# vilnius_rev_B.net
KiCad netlist of a schematic drawn in EAGLE
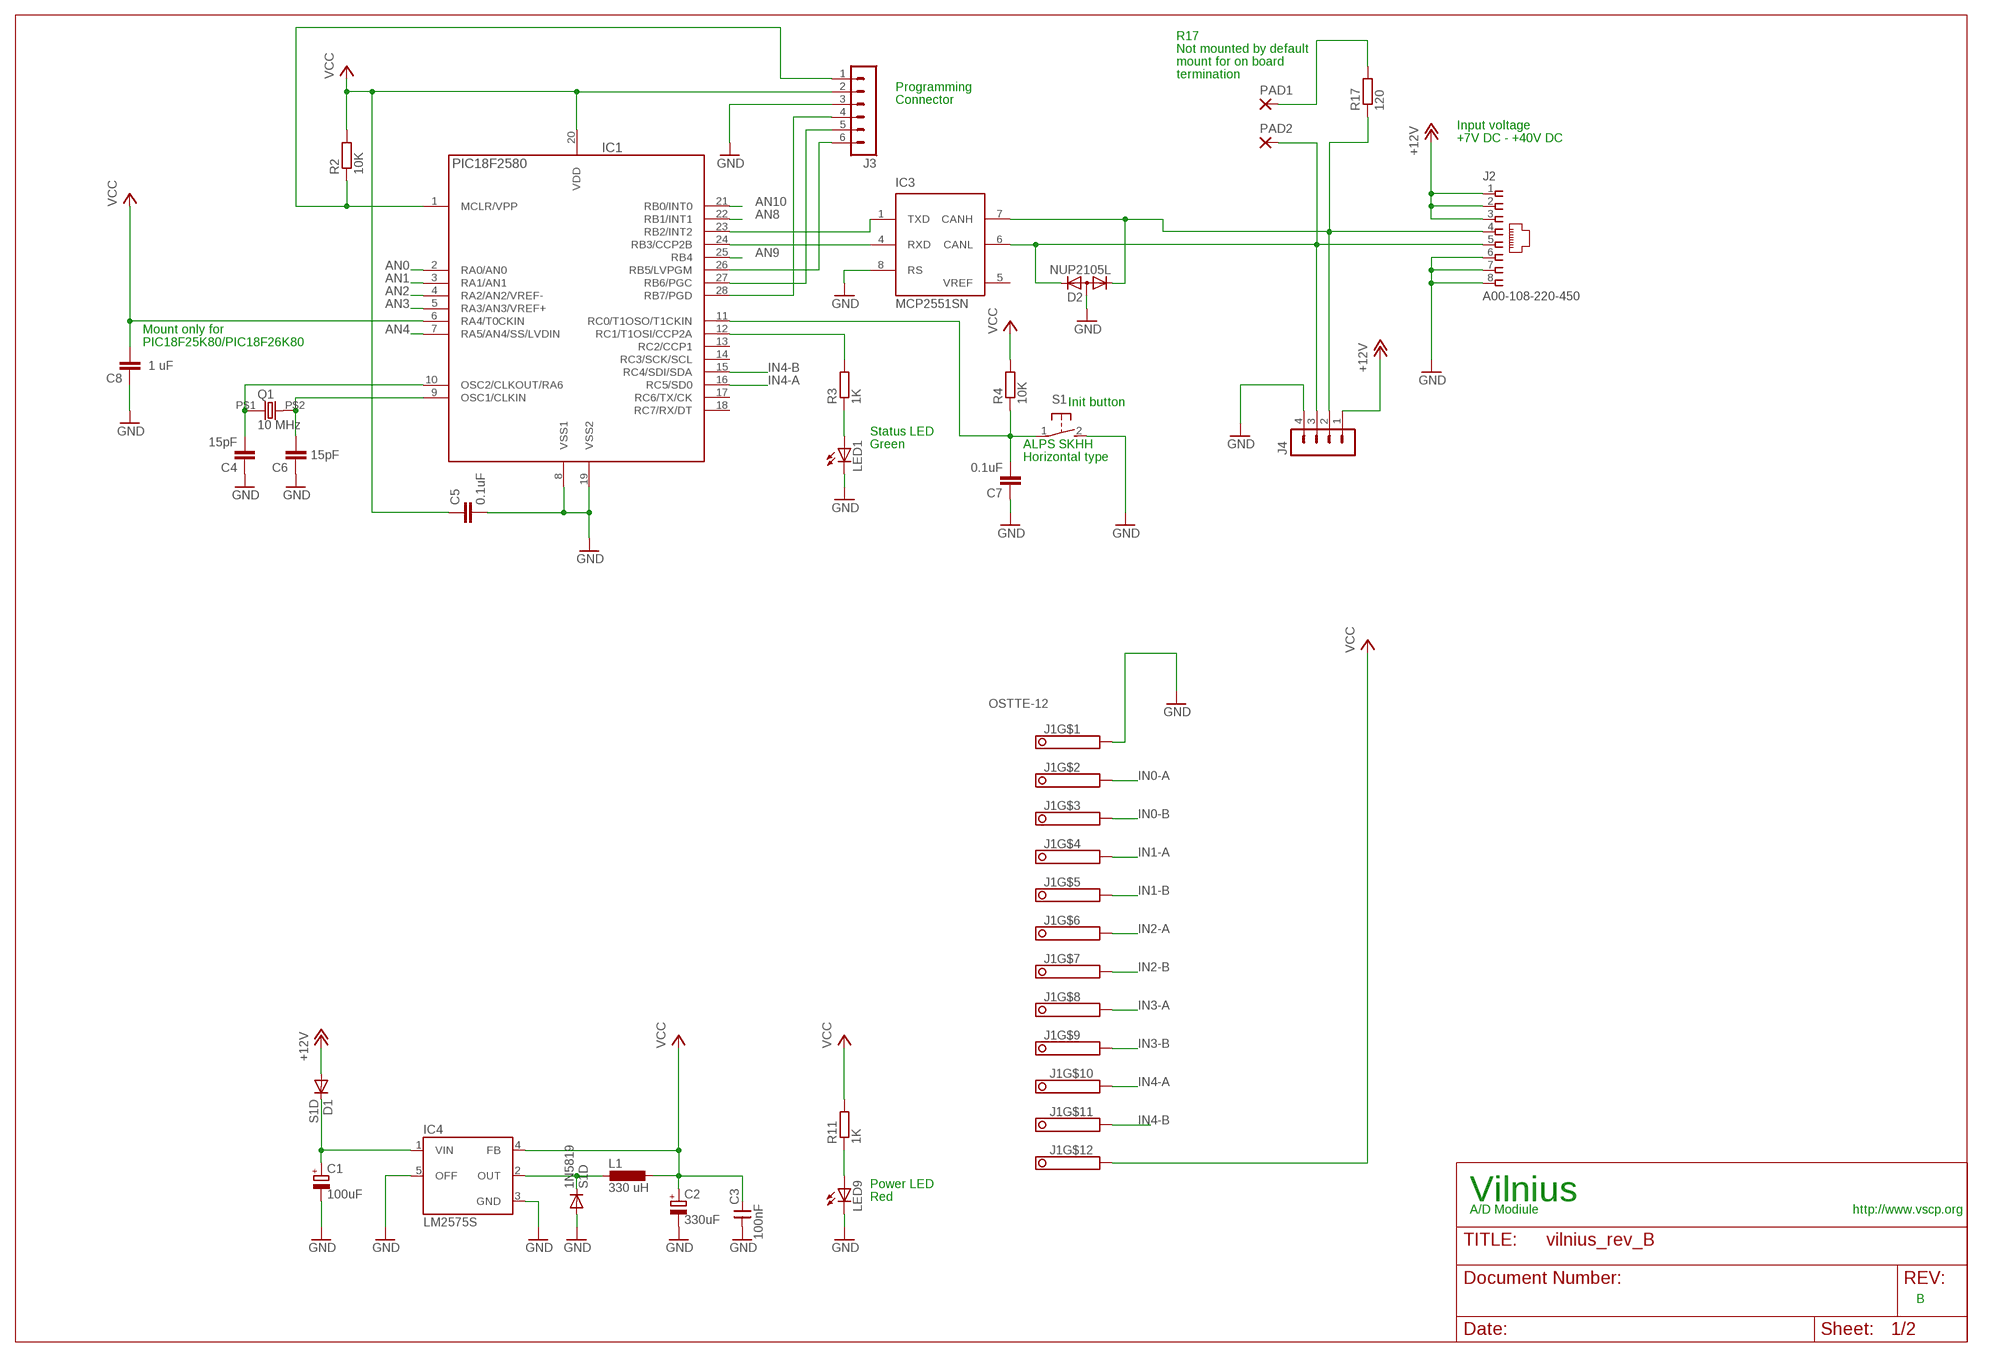
[diagram p0: schematic, sheet 1]
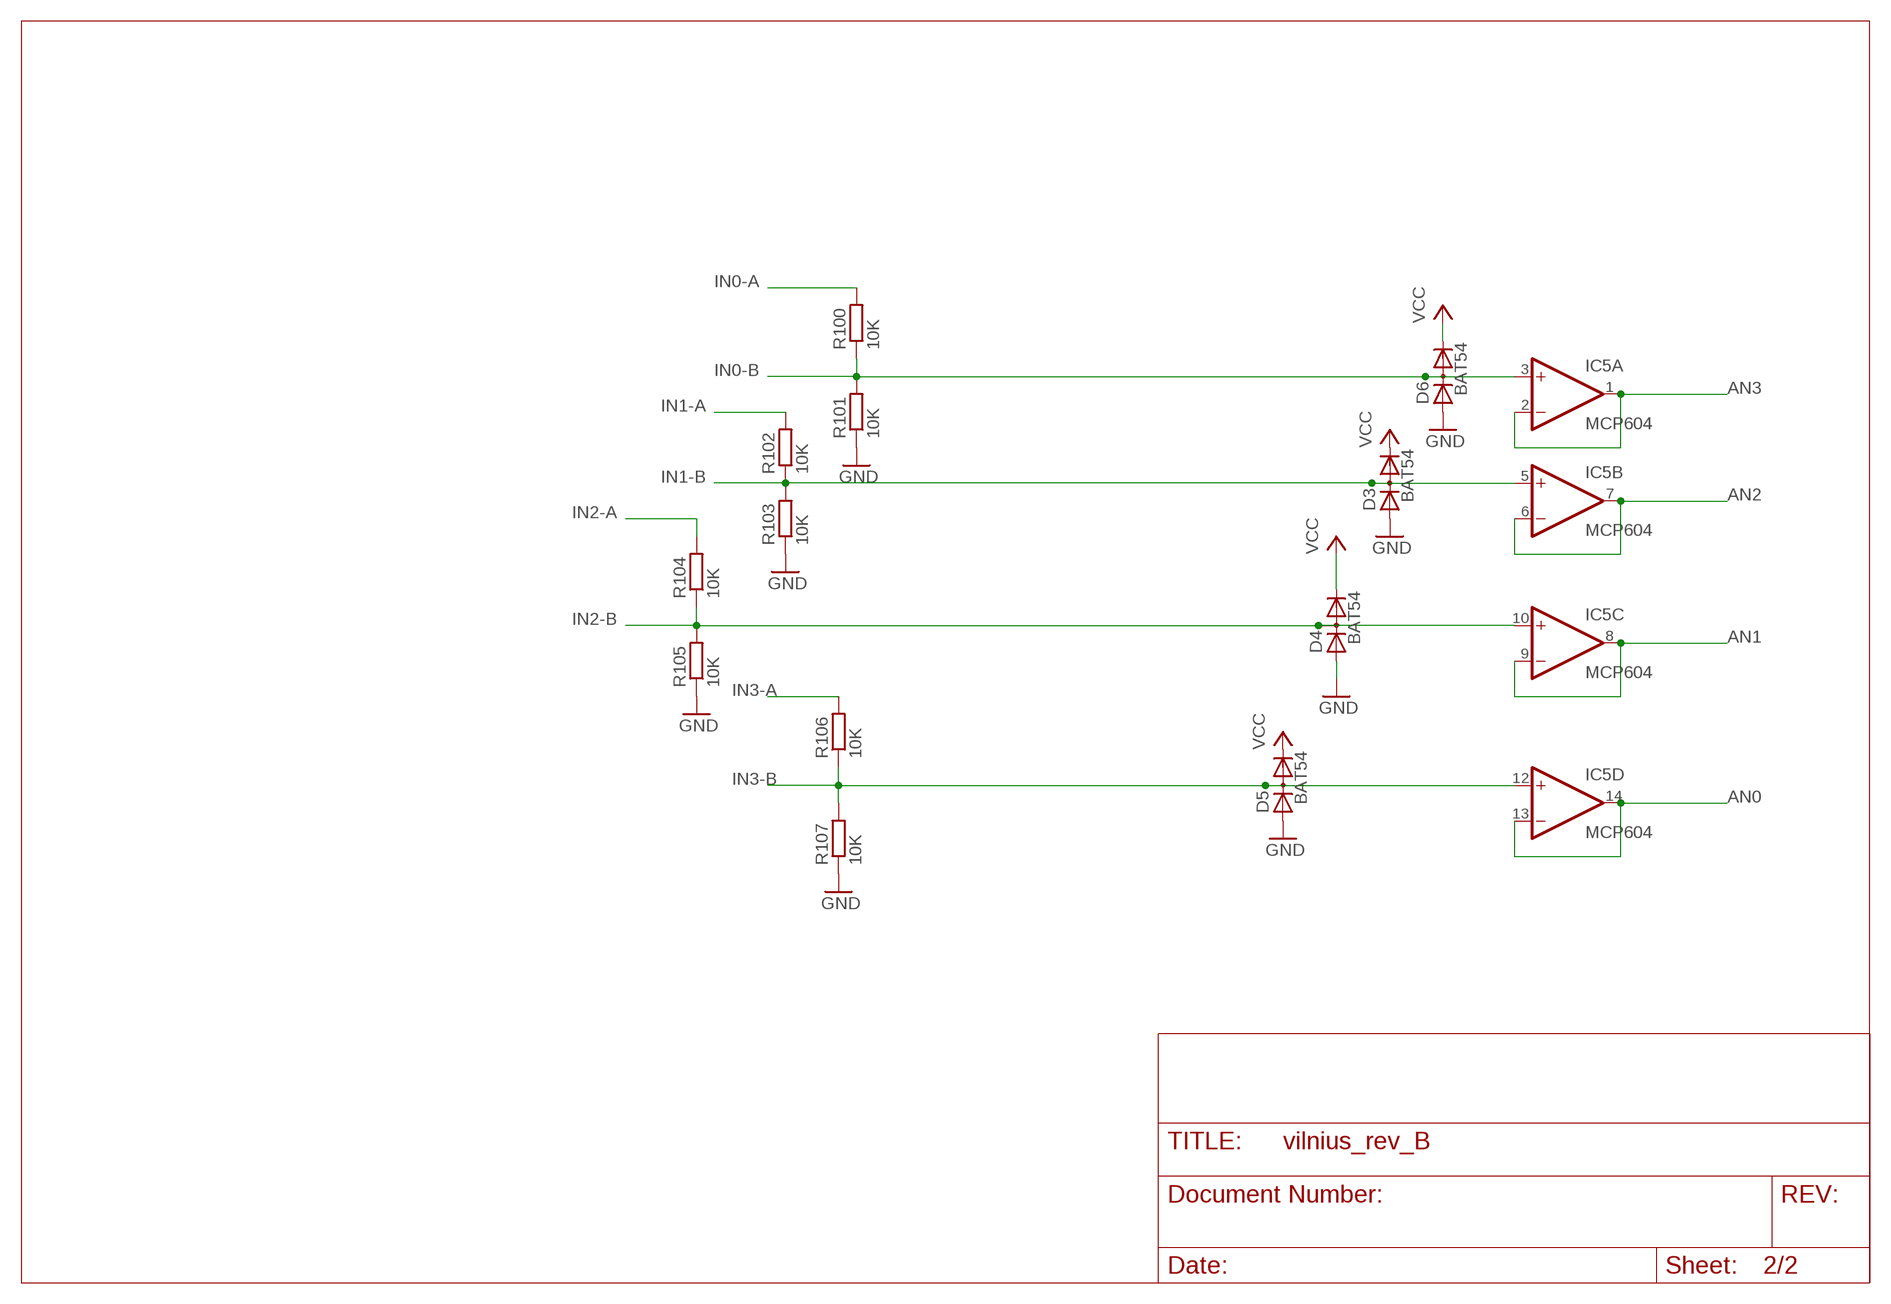
[diagram p1: schematic, sheet 2]

(export (version "E")
  (design (tool "Eeschema 10.0.6"))
  (components
    (comp (ref "1N5819")
      (value "S1D")
      (footprint "eagle-import:SOD123")
      (libsource (lib "eagle-import") (part "DIODE-SOD123"))
    )
    (comp (ref "C1")
      (value "100uF")
      (footprint "eagle-import:PANASONIC_D")
      (libsource (lib "eagle-import") (part "CPOL-EUD"))
    )
    (comp (ref "C2")
      (value "330uF")
      (footprint "eagle-import:PANASONIC_D")
      (libsource (lib "eagle-import") (part "CPOL-EUD"))
    )
    (comp (ref "C3")
      (value "100nF")
      (footprint "eagle-import:0805")
      (libsource (lib "eagle-import") (part "CNP-0805"))
    )
    (comp (ref "C4")
      (value "15pF")
      (footprint "eagle-import:C0805")
      (libsource (lib "eagle-import") (part "C-EUC0805"))
    )
    (comp (ref "C5")
      (value "0.1uF")
      (footprint "eagle-import:C0805")
      (libsource (lib "eagle-import") (part "C-EUC0805"))
    )
    (comp (ref "C6")
      (value "15pF")
      (footprint "eagle-import:C0805")
      (libsource (lib "eagle-import") (part "C-EUC0805"))
    )
    (comp (ref "C7")
      (value "0.1uF")
      (footprint "eagle-import:C0805")
      (libsource (lib "eagle-import") (part "C-EUC0805"))
    )
    (comp (ref "C8")
      (value "1 uF")
      (footprint "eagle-import:C0805")
      (libsource (lib "eagle-import") (part "C-EUC0805"))
    )
    (comp (ref "D1")
      (value "S1D")
      (footprint "eagle-import:SOD123")
      (libsource (lib "eagle-import") (part "DIODE-SOD123"))
    )
    (comp (ref "D2")
      (value "NUP2105L")
      (footprint "eagle-import:SOT23@1")
      (libsource (lib "eagle-import") (part "DIODE-2CA|ACSOT23"))
    )
    (comp (ref "IC1")
      (value "PIC18F2580")
      (footprint "eagle-import:SO28")
      (libsource (lib "eagle-import") (part "PIC18F252-?I/SOL"))
    )
    (comp (ref "IC3")
      (value "MCP2551SN")
      (footprint "eagle-import:SO-08")
      (libsource (lib "eagle-import") (part "MCP2551SN"))
    )
    (comp (ref "IC4")
      (value "LM2575S")
      (footprint "eagle-import:TO263-5")
      (libsource (lib "eagle-import") (part "LM2575S"))
    )
    (comp (ref "J1")
      (value "OSTTE-12")
      (footprint "eagle-import:PINHEAD-12")
      (libsource (lib "eagle-import") (part "OSTTE-12"))
    )
    (comp (ref "J2")
      (value "A00-108-220-450")
      (footprint "eagle-import:RJ-45")
      (libsource (lib "eagle-import") (part "A00-108-220-450"))
    )
    (comp (ref "J3")
      (value "MA06-1")
      (footprint "eagle-import:MA06-1")
      (libsource (lib "eagle-import") (part "MA06-1"))
    )
    (comp (ref "J4")
      (value "MA04-1")
      (footprint "eagle-import:MA04-1")
      (libsource (lib "eagle-import") (part "MA04-1"))
    )
    (comp (ref "L1")
      (value "330 uH")
      (footprint "eagle-import:DO3316P")
      (libsource (lib "eagle-import") (part "DO3316P"))
    )
    (comp (ref "LED1")
      (value "LEDCHIP-LED0805")
      (footprint "eagle-import:CHIP-LED0805")
      (libsource (lib "eagle-import") (part "LEDCHIP-LED0805"))
    )
    (comp (ref "LED9")
      (value "LEDCHIP-LED0805")
      (footprint "eagle-import:CHIP-LED0805")
      (libsource (lib "eagle-import") (part "LEDCHIP-LED0805"))
    )
    (comp (ref "PAD1")
      (value "1,6/0,8")
      (footprint "eagle-import:1,6_0,8")
      (libsource (lib "eagle-import") (part "1,6/0,8"))
    )
    (comp (ref "PAD2")
      (value "1,6/0,8")
      (footprint "eagle-import:1,6_0,8")
      (libsource (lib "eagle-import") (part "1,6/0,8"))
    )
    (comp (ref "Q1")
      (value "10 MHz")
      (footprint "eagle-import:9C")
      (libsource (lib "eagle-import") (part "HC-49S"))
    )
    (comp (ref "R2")
      (value "10K")
      (footprint "eagle-import:R0805")
      (libsource (lib "eagle-import") (part "R-EU_R0805"))
    )
    (comp (ref "R3")
      (value "1K")
      (footprint "eagle-import:R0805")
      (libsource (lib "eagle-import") (part "R-EU_R0805"))
    )
    (comp (ref "R4")
      (value "10K")
      (footprint "eagle-import:R0805")
      (libsource (lib "eagle-import") (part "R-EU_R0805"))
    )
    (comp (ref "R11")
      (value "1K")
      (footprint "eagle-import:R0805")
      (libsource (lib "eagle-import") (part "R-EU_R0805"))
    )
    (comp (ref "R17")
      (value "120")
      (footprint "eagle-import:R0805")
      (libsource (lib "eagle-import") (part "R-EU_R0805"))
    )
    (comp (ref "S1")
      (value "31-XX")
      (footprint "eagle-import:B3F-31XX")
      (fields (field (name "MPN") "B3F-3100"))
      (libsource (lib "eagle-import") (part "31-XX"))
    )
    (comp (ref "D3")
      (value "BAT54")
      (footprint "eagle-import:SOT23")
      (libsource (lib "eagle-import") (part "BAV199"))
    )
    (comp (ref "D4")
      (value "BAT54")
      (footprint "eagle-import:SOT23")
      (libsource (lib "eagle-import") (part "BAV199"))
    )
    (comp (ref "D5")
      (value "BAT54")
      (footprint "eagle-import:SOT23")
      (libsource (lib "eagle-import") (part "BAV199"))
    )
    (comp (ref "D6")
      (value "BAT54")
      (footprint "eagle-import:SOT23")
      (libsource (lib "eagle-import") (part "BAV199"))
    )
    (comp (ref "IC5")
      (value "MCP604")
      (footprint "eagle-import:SO14")
      (libsource (lib "eagle-import") (part "4AMP_P4+11D"))
    )
    (comp (ref "R100")
      (value "10K")
      (footprint "eagle-import:R0805")
      (libsource (lib "eagle-import") (part "R-EU_R0805"))
    )
    (comp (ref "R101")
      (value "10K")
      (footprint "eagle-import:R0805")
      (libsource (lib "eagle-import") (part "R-EU_R0805"))
    )
    (comp (ref "R102")
      (value "10K")
      (footprint "eagle-import:R0805")
      (libsource (lib "eagle-import") (part "R-EU_R0805"))
    )
    (comp (ref "R103")
      (value "10K")
      (footprint "eagle-import:R0805")
      (libsource (lib "eagle-import") (part "R-EU_R0805"))
    )
    (comp (ref "R104")
      (value "10K")
      (footprint "eagle-import:R0805")
      (libsource (lib "eagle-import") (part "R-EU_R0805"))
    )
    (comp (ref "R105")
      (value "10K")
      (footprint "eagle-import:R0805")
      (libsource (lib "eagle-import") (part "R-EU_R0805"))
    )
    (comp (ref "R106")
      (value "10K")
      (footprint "eagle-import:R0805")
      (libsource (lib "eagle-import") (part "R-EU_R0805"))
    )
    (comp (ref "R107")
      (value "10K")
      (footprint "eagle-import:R0805")
      (libsource (lib "eagle-import") (part "R-EU_R0805"))
    )
  )
  (nets
    (net (code "1") (name "+12V") (class "Default")
      (node (ref "D1") (pin "A") (pinfunction "A_A") (pintype "passive"))
      (node (ref "J2") (pin "1") (pinfunction "1_1") (pintype "passive"))
      (node (ref "J2") (pin "2") (pinfunction "2_2") (pintype "passive"))
      (node (ref "J2") (pin "3") (pinfunction "3_3") (pintype "passive"))
      (node (ref "J4") (pin "1") (pinfunction "1_1") (pintype "passive"))
    )
    (net (code "2") (name "AN0") (class "Default")
      (node (ref "IC1") (pin "2") (pinfunction "RA0/AN0_2") (pintype "bidirectional"))
      (node (ref "IC5") (pin "13") (pinfunction "-IN_13") (pintype "input"))
      (node (ref "IC5") (pin "14") (pinfunction "OUT_14") (pintype "output"))
    )
    (net (code "3") (name "AN1") (class "Default")
      (node (ref "IC1") (pin "3") (pinfunction "RA1/AN1_3") (pintype "bidirectional"))
      (node (ref "IC5") (pin "8") (pinfunction "OUT_8") (pintype "output"))
      (node (ref "IC5") (pin "9") (pinfunction "-IN_9") (pintype "input"))
    )
    (net (code "4") (name "AN2") (class "Default")
      (node (ref "IC1") (pin "4") (pinfunction "RA2/AN2/VREF-_4") (pintype "bidirectional"))
      (node (ref "IC5") (pin "6") (pinfunction "-IN_6") (pintype "input"))
      (node (ref "IC5") (pin "7") (pinfunction "OUT_7") (pintype "output"))
    )
    (net (code "5") (name "AN3") (class "Default")
      (node (ref "IC1") (pin "5") (pinfunction "RA3/AN3/VREF+_5") (pintype "bidirectional"))
      (node (ref "IC5") (pin "1") (pinfunction "OUT_1") (pintype "output"))
      (node (ref "IC5") (pin "2") (pinfunction "-IN_2") (pintype "input"))
    )
    (net (code "6") (name "AN4") (class "Default")
      (node (ref "IC1") (pin "7") (pinfunction "RA5/AN4/SS/LVDIN_7") (pintype "bidirectional"))
    )
    (net (code "7") (name "AN8") (class "Default")
      (node (ref "IC1") (pin "22") (pinfunction "RB1/INT1_22") (pintype "bidirectional"))
    )
    (net (code "8") (name "AN9") (class "Default")
      (node (ref "IC1") (pin "25") (pinfunction "RB4_25") (pintype "bidirectional"))
    )
    (net (code "9") (name "AN10") (class "Default")
      (node (ref "IC1") (pin "21") (pinfunction "RB0/INT0_21") (pintype "bidirectional"))
    )
    (net (code "10") (name "GND") (class "Default")
      (node (ref "1N5819") (pin "A") (pinfunction "A_A") (pintype "passive"))
      (node (ref "C1") (pin "-") (pinfunction "-_-") (pintype "passive"))
      (node (ref "C2") (pin "-") (pinfunction "-_-") (pintype "passive"))
      (node (ref "C3") (pin "1") (pinfunction "1_1") (pintype "passive"))
      (node (ref "C4") (pin "1") (pinfunction "1_1") (pintype "passive"))
      (node (ref "C5") (pin "2") (pinfunction "2_2") (pintype "passive"))
      (node (ref "C6") (pin "1") (pinfunction "1_1") (pintype "passive"))
      (node (ref "C7") (pin "1") (pinfunction "1_1") (pintype "passive"))
      (node (ref "C8") (pin "1") (pinfunction "1_1") (pintype "passive"))
      (node (ref "D2") (pin "3") (pinfunction "A_3") (pintype "passive"))
      (node (ref "D3") (pin "1") (pinfunction "A_1") (pintype "passive"))
      (node (ref "D4") (pin "1") (pinfunction "A_1") (pintype "passive"))
      (node (ref "D5") (pin "1") (pinfunction "A_1") (pintype "passive"))
      (node (ref "D6") (pin "1") (pinfunction "A_1") (pintype "passive"))
      (node (ref "IC1") (pin "19") (pinfunction "VSS2_19") (pintype "power_in"))
      (node (ref "IC1") (pin "8") (pinfunction "VSS1_8") (pintype "power_in"))
      (node (ref "IC3") (pin "8") (pinfunction "RS_8") (pintype "input"))
      (node (ref "IC4") (pin "3") (pinfunction "GND_3") (pintype "power_in"))
      (node (ref "IC4") (pin "5") (pinfunction "OFF_5") (pintype "input"))
      (node (ref "J1") (pin "1") (pinfunction "K_1") (pintype "passive"))
      (node (ref "J2") (pin "6") (pinfunction "6_6") (pintype "passive"))
      (node (ref "J2") (pin "7") (pinfunction "7_7") (pintype "passive"))
      (node (ref "J2") (pin "8") (pinfunction "8_8") (pintype "passive"))
      (node (ref "J3") (pin "3") (pinfunction "3_3") (pintype "passive"))
      (node (ref "J4") (pin "4") (pinfunction "4_4") (pintype "passive"))
      (node (ref "LED1") (pin "C") (pinfunction "C_C") (pintype "passive"))
      (node (ref "LED9") (pin "C") (pinfunction "C_C") (pintype "passive"))
      (node (ref "R101") (pin "1") (pinfunction "1_1") (pintype "passive"))
      (node (ref "R103") (pin "1") (pinfunction "1_1") (pintype "passive"))
      (node (ref "R105") (pin "1") (pinfunction "1_1") (pintype "passive"))
      (node (ref "R107") (pin "1") (pinfunction "1_1") (pintype "passive"))
      (node (ref "S1") (pin "2") (pinfunction "S_2") (pintype "passive"))
    )
    (net (code "11") (name "IN0-A") (class "Default")
      (node (ref "J1") (pin "2") (pinfunction "K_2") (pintype "passive"))
      (node (ref "R100") (pin "2") (pinfunction "2_2") (pintype "passive"))
    )
    (net (code "12") (name "IN0-B") (class "Default")
      (node (ref "D6") (pin "3") (pinfunction "AC_3") (pintype "passive"))
      (node (ref "IC5") (pin "3") (pinfunction "+IN_3") (pintype "input"))
      (node (ref "J1") (pin "3") (pinfunction "K_3") (pintype "passive"))
      (node (ref "R100") (pin "1") (pinfunction "1_1") (pintype "passive"))
      (node (ref "R101") (pin "2") (pinfunction "2_2") (pintype "passive"))
    )
    (net (code "13") (name "IN1-A") (class "Default")
      (node (ref "J1") (pin "4") (pinfunction "K_4") (pintype "passive"))
      (node (ref "R102") (pin "2") (pinfunction "2_2") (pintype "passive"))
    )
    (net (code "14") (name "IN1-B") (class "Default")
      (node (ref "D3") (pin "3") (pinfunction "AC_3") (pintype "passive"))
      (node (ref "IC5") (pin "5") (pinfunction "+IN_5") (pintype "input"))
      (node (ref "J1") (pin "5") (pinfunction "K_5") (pintype "passive"))
      (node (ref "R102") (pin "1") (pinfunction "1_1") (pintype "passive"))
      (node (ref "R103") (pin "2") (pinfunction "2_2") (pintype "passive"))
    )
    (net (code "15") (name "IN2-A") (class "Default")
      (node (ref "J1") (pin "6") (pinfunction "K_6") (pintype "passive"))
      (node (ref "R104") (pin "2") (pinfunction "2_2") (pintype "passive"))
    )
    (net (code "16") (name "IN2-B") (class "Default")
      (node (ref "D4") (pin "3") (pinfunction "AC_3") (pintype "passive"))
      (node (ref "IC5") (pin "10") (pinfunction "+IN_10") (pintype "input"))
      (node (ref "J1") (pin "7") (pinfunction "K_7") (pintype "passive"))
      (node (ref "R104") (pin "1") (pinfunction "1_1") (pintype "passive"))
      (node (ref "R105") (pin "2") (pinfunction "2_2") (pintype "passive"))
    )
    (net (code "17") (name "IN3-A") (class "Default")
      (node (ref "J1") (pin "8") (pinfunction "K_8") (pintype "passive"))
      (node (ref "R106") (pin "2") (pinfunction "2_2") (pintype "passive"))
    )
    (net (code "18") (name "IN3-B") (class "Default")
      (node (ref "D5") (pin "3") (pinfunction "AC_3") (pintype "passive"))
      (node (ref "IC5") (pin "12") (pinfunction "+IN_12") (pintype "input"))
      (node (ref "J1") (pin "9") (pinfunction "K_9") (pintype "passive"))
      (node (ref "R106") (pin "1") (pinfunction "1_1") (pintype "passive"))
      (node (ref "R107") (pin "2") (pinfunction "2_2") (pintype "passive"))
    )
    (net (code "19") (name "IN4-A") (class "Default")
      (node (ref "IC1") (pin "16") (pinfunction "RC5/SD0_16") (pintype "bidirectional"))
      (node (ref "J1") (pin "10") (pinfunction "K_10") (pintype "passive"))
    )
    (net (code "20") (name "IN4-B") (class "Default")
      (node (ref "IC1") (pin "15") (pinfunction "RC4/SDI/SDA_15") (pintype "bidirectional"))
      (node (ref "J1") (pin "11") (pinfunction "K_11") (pintype "passive"))
    )
    (net (code "21") (name "Net-(D2-K1)") (class "Default")
      (node (ref "D2") (pin "1") (pinfunction "K1_1") (pintype "passive"))
      (node (ref "IC3") (pin "7") (pinfunction "CANH_7") (pintype "bidirectional"))
      (node (ref "J2") (pin "4") (pinfunction "4_4") (pintype "passive"))
      (node (ref "J4") (pin "2") (pinfunction "2_2") (pintype "passive"))
      (node (ref "R17") (pin "1") (pinfunction "1_1") (pintype "passive"))
    )
    (net (code "22") (name "Net-(D2-K2)") (class "Default")
      (node (ref "D2") (pin "2") (pinfunction "K2_2") (pintype "passive"))
      (node (ref "IC3") (pin "6") (pinfunction "CANL_6") (pintype "bidirectional"))
      (node (ref "J2") (pin "5") (pinfunction "5_5") (pintype "passive"))
      (node (ref "J4") (pin "3") (pinfunction "3_3") (pintype "passive"))
      (node (ref "PAD2") (pin "1") (pinfunction "P_1") (pintype "passive"))
    )
    (net (code "23") (name "Net-(IC1-MCLR{slash}VPP)") (class "Default")
      (node (ref "IC1") (pin "1") (pinfunction "MCLR/VPP_1") (pintype "input"))
      (node (ref "J3") (pin "1") (pinfunction "1_1") (pintype "passive"))
      (node (ref "R2") (pin "1") (pinfunction "1_1") (pintype "passive"))
    )
    (net (code "24") (name "Net-(IC1-OSC1{slash}CLKIN)") (class "Default")
      (node (ref "C6") (pin "2") (pinfunction "2_2") (pintype "passive"))
      (node (ref "IC1") (pin "9") (pinfunction "OSC1/CLKIN_9") (pintype "input"))
      (node (ref "Q1") (pin "P$2") (pinfunction "2_P$2") (pintype "passive"))
    )
    (net (code "25") (name "Net-(IC1-OSC2{slash}CLKOUT{slash}RA6)") (class "Default")
      (node (ref "C4") (pin "2") (pinfunction "2_2") (pintype "passive"))
      (node (ref "IC1") (pin "10") (pinfunction "OSC2/CLKOUT/RA6_10") (pintype "output"))
      (node (ref "Q1") (pin "P$1") (pinfunction "1_P$1") (pintype "passive"))
    )
    (net (code "26") (name "Net-(IC1-RB2{slash}INT2)") (class "Default")
      (node (ref "IC1") (pin "23") (pinfunction "RB2/INT2_23") (pintype "bidirectional"))
      (node (ref "IC3") (pin "1") (pinfunction "TXD_1") (pintype "input"))
    )
    (net (code "27") (name "Net-(IC1-RB3{slash}CCP2B)") (class "Default")
      (node (ref "IC1") (pin "24") (pinfunction "RB3/CCP2B_24") (pintype "bidirectional"))
      (node (ref "IC3") (pin "4") (pinfunction "RXD_4") (pintype "output"))
    )
    (net (code "28") (name "Net-(IC1-RB5{slash}LVPGM)") (class "Default")
      (node (ref "IC1") (pin "26") (pinfunction "RB5/LVPGM_26") (pintype "bidirectional"))
      (node (ref "J3") (pin "6") (pinfunction "6_6") (pintype "passive"))
    )
    (net (code "29") (name "Net-(IC1-RB6{slash}PGC)") (class "Default")
      (node (ref "IC1") (pin "27") (pinfunction "RB6/PGC_27") (pintype "bidirectional"))
      (node (ref "J3") (pin "5") (pinfunction "5_5") (pintype "passive"))
    )
    (net (code "30") (name "Net-(IC1-RB7{slash}PGD)") (class "Default")
      (node (ref "IC1") (pin "28") (pinfunction "RB7/PGD_28") (pintype "bidirectional"))
      (node (ref "J3") (pin "4") (pinfunction "4_4") (pintype "passive"))
    )
    (net (code "31") (name "Net-(IC1-RC0{slash}T1OSO{slash}T1CKIN)") (class "Default")
      (node (ref "C7") (pin "2") (pinfunction "2_2") (pintype "passive"))
      (node (ref "IC1") (pin "11") (pinfunction "RC0/T1OSO/T1CKIN_11") (pintype "bidirectional"))
      (node (ref "R4") (pin "1") (pinfunction "1_1") (pintype "passive"))
      (node (ref "S1") (pin "1") (pinfunction "P_1") (pintype "passive"))
    )
    (net (code "32") (name "Net-(IC1-RC1{slash}T1OSI{slash}CCP2A)") (class "Default")
      (node (ref "IC1") (pin "12") (pinfunction "RC1/T1OSI/CCP2A_12") (pintype "bidirectional"))
      (node (ref "R3") (pin "2") (pinfunction "2_2") (pintype "passive"))
    )
    (net (code "33") (name "Net-(IC4-OUT)") (class "Default")
      (node (ref "1N5819") (pin "C") (pinfunction "C_C") (pintype "passive"))
      (node (ref "IC4") (pin "2") (pinfunction "OUT_2") (pintype "output"))
      (node (ref "L1") (pin "1") (pinfunction "1_1") (pintype "passive"))
    )
    (net (code "34") (name "Net-(IC4-VIN)") (class "Default")
      (node (ref "C1") (pin "+") (pinfunction "+_+") (pintype "passive"))
      (node (ref "D1") (pin "C") (pinfunction "C_C") (pintype "passive"))
      (node (ref "IC4") (pin "1") (pinfunction "VIN_1") (pintype "power_in"))
    )
    (net (code "35") (name "Net-(LED1-PadA)") (class "Default")
      (node (ref "LED1") (pin "A") (pinfunction "A_A") (pintype "passive"))
      (node (ref "R3") (pin "1") (pinfunction "1_1") (pintype "passive"))
    )
    (net (code "36") (name "Net-(LED9-PadA)") (class "Default")
      (node (ref "LED9") (pin "A") (pinfunction "A_A") (pintype "passive"))
      (node (ref "R11") (pin "1") (pinfunction "1_1") (pintype "passive"))
    )
    (net (code "37") (name "Net-(PAD1-P)") (class "Default")
      (node (ref "PAD1") (pin "1") (pinfunction "P_1") (pintype "passive"))
      (node (ref "R17") (pin "2") (pinfunction "2_2") (pintype "passive"))
    )
    (net (code "38") (name "VCC") (class "Default")
      (node (ref "C2") (pin "+") (pinfunction "+_+") (pintype "passive"))
      (node (ref "C3") (pin "2") (pinfunction "2_2") (pintype "passive"))
      (node (ref "C5") (pin "1") (pinfunction "1_1") (pintype "passive"))
      (node (ref "C8") (pin "2") (pinfunction "2_2") (pintype "passive"))
      (node (ref "D3") (pin "2") (pinfunction "C_2") (pintype "passive"))
      (node (ref "D4") (pin "2") (pinfunction "C_2") (pintype "passive"))
      (node (ref "D5") (pin "2") (pinfunction "C_2") (pintype "passive"))
      (node (ref "D6") (pin "2") (pinfunction "C_2") (pintype "passive"))
      (node (ref "IC1") (pin "20") (pinfunction "VDD_20") (pintype "power_in"))
      (node (ref "IC1") (pin "6") (pinfunction "RA4/T0CKIN_6") (pintype "open_collector"))
      (node (ref "IC4") (pin "4") (pinfunction "FB_4") (pintype "input"))
      (node (ref "J1") (pin "12") (pinfunction "K_12") (pintype "passive"))
      (node (ref "J3") (pin "2") (pinfunction "2_2") (pintype "passive"))
      (node (ref "L1") (pin "2") (pinfunction "2_2") (pintype "passive"))
      (node (ref "R11") (pin "2") (pinfunction "2_2") (pintype "passive"))
      (node (ref "R2") (pin "2") (pinfunction "2_2") (pintype "passive"))
      (node (ref "R4") (pin "2") (pinfunction "2_2") (pintype "passive"))
    )
    (net (code "39") (name "VREF") (class "Default")
      (node (ref "IC3") (pin "5") (pinfunction "VREF_5") (pintype "power_in"))
    )
    (net (code "40") (name "unconnected-(IC1-RC2{slash}CCP1-Pad13)") (class "Default")
      (node (ref "IC1") (pin "13") (pinfunction "RC2/CCP1_13") (pintype "bidirectional"))
    )
    (net (code "41") (name "unconnected-(IC1-RC3{slash}SCK{slash}SCL-Pad14)") (class "Default")
      (node (ref "IC1") (pin "14") (pinfunction "RC3/SCK/SCL_14") (pintype "bidirectional"))
    )
    (net (code "42") (name "unconnected-(IC1-RC6{slash}TX{slash}CK-Pad17)") (class "Default")
      (node (ref "IC1") (pin "17") (pinfunction "RC6/TX/CK_17") (pintype "bidirectional"))
    )
    (net (code "43") (name "unconnected-(IC1-RC7{slash}RX{slash}DT-Pad18)") (class "Default")
      (node (ref "IC1") (pin "18") (pinfunction "RC7/RX/DT_18") (pintype "bidirectional"))
    )
  )
)
